# Attenuator.net
KiCad netlist of a schematic drawn in EAGLE
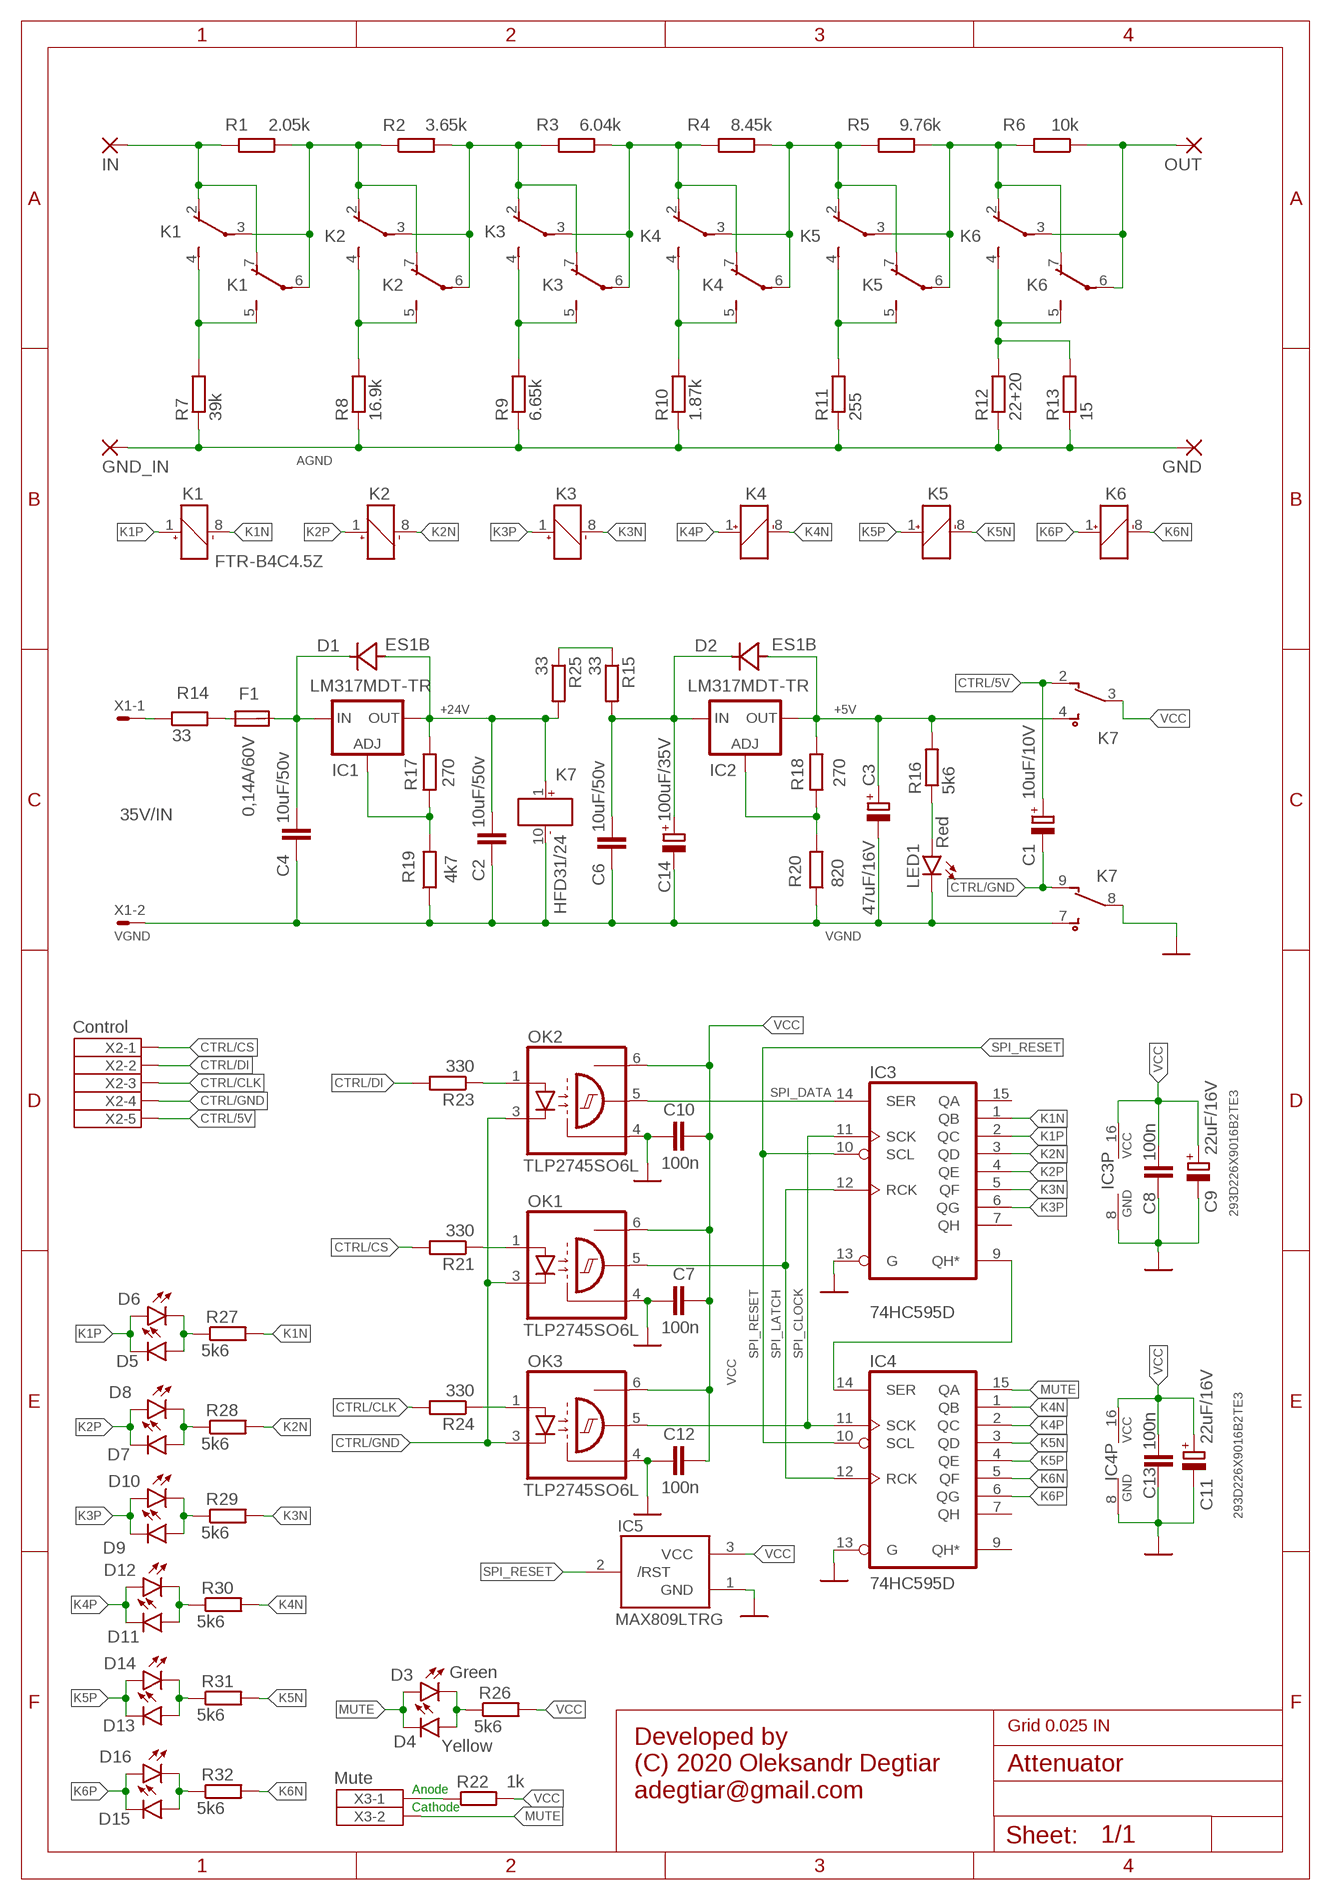
[diagram p0: schematic, sheet 1]

(export (version "E")
  (design (tool "Eeschema 10.0.6"))
  (components
    (comp (ref "C1")
      (value "10uF/10V")
      (footprint "eagle-import:SMC_A")
      (fields (field (name "PARTNAME") "TAJA106K010RNJ"))
      (libsource (lib "eagle-import") (part "rcl_334_CPOL-EUSMCA"))
    )
    (comp (ref "C2")
      (value "10uF/50v")
      (footprint "eagle-import:C1206")
      (libsource (lib "eagle-import") (part "C-EUC1206"))
    )
    (comp (ref "C3")
      (value "47uF/16V")
      (footprint "eagle-import:SMC_C")
      (libsource (lib "eagle-import") (part "rcl_334_CPOL-EUSMCC"))
    )
    (comp (ref "C4")
      (value "10uF/50v")
      (footprint "eagle-import:C1206")
      (libsource (lib "eagle-import") (part "C-EUC1206"))
    )
    (comp (ref "C6")
      (value "10uF/50v")
      (footprint "eagle-import:C1206")
      (libsource (lib "eagle-import") (part "C-EUC1206"))
    )
    (comp (ref "C7")
      (value "100n")
      (footprint "eagle-import:C0603")
      (libsource (lib "eagle-import") (part "C-EUC0603"))
    )
    (comp (ref "C8")
      (value "100n")
      (footprint "eagle-import:C0603")
      (libsource (lib "eagle-import") (part "C-EUC0603"))
    )
    (comp (ref "C9")
      (value "22uF/16V")
      (footprint "eagle-import:SMC_B")
      (fields (field (name "PARTNAME") "293D226X9016B2TE3"))
      (libsource (lib "eagle-import") (part "rcl_334_CPOL-EUSMCB"))
    )
    (comp (ref "C10")
      (value "100n")
      (footprint "eagle-import:C0603")
      (libsource (lib "eagle-import") (part "C-EUC0603"))
    )
    (comp (ref "C11")
      (value "22uF/16V")
      (footprint "eagle-import:SMC_B")
      (fields (field (name "PARTNAME") "293D226X9016B2TE3"))
      (libsource (lib "eagle-import") (part "rcl_334_CPOL-EUSMCB"))
    )
    (comp (ref "C12")
      (value "100n")
      (footprint "eagle-import:C0603")
      (libsource (lib "eagle-import") (part "C-EUC0603"))
    )
    (comp (ref "C13")
      (value "100n")
      (footprint "eagle-import:C0603")
      (libsource (lib "eagle-import") (part "C-EUC0603"))
    )
    (comp (ref "C14")
      (value "100uF/35V")
      (footprint "eagle-import:UD-6,3X5,8_NICHICON")
      (fields (field (name "PARTNAME") "EEEFK1V101XP"))
      (libsource (lib "eagle-import") (part "CPOL-EUUD-6,3X8,8"))
    )
    (comp (ref "D1")
      (value "ES1B")
      (footprint "eagle-import:SMA")
      (libsource (lib "eagle-import") (part "MBRA340T3"))
    )
    (comp (ref "D2")
      (value "ES1B")
      (footprint "eagle-import:SMA")
      (libsource (lib "eagle-import") (part "MBRA340T3"))
    )
    (comp (ref "D3")
      (value "Green")
      (footprint "eagle-import:CHIPLED_0805")
      (libsource (lib "eagle-import") (part "LEDCHIPLED_0805"))
    )
    (comp (ref "D4")
      (value "Yellow")
      (footprint "eagle-import:CHIPLED_0805")
      (libsource (lib "eagle-import") (part "LEDCHIPLED_0805"))
    )
    (comp (ref "D5")
      (value "LEDCHIPLED_0805")
      (footprint "eagle-import:CHIPLED_0805")
      (libsource (lib "eagle-import") (part "LEDCHIPLED_0805"))
    )
    (comp (ref "D6")
      (value "LEDCHIPLED_0805")
      (footprint "eagle-import:CHIPLED_0805")
      (libsource (lib "eagle-import") (part "LEDCHIPLED_0805"))
    )
    (comp (ref "D7")
      (value "LEDCHIPLED_0805")
      (footprint "eagle-import:CHIPLED_0805")
      (libsource (lib "eagle-import") (part "LEDCHIPLED_0805"))
    )
    (comp (ref "D8")
      (value "LEDCHIPLED_0805")
      (footprint "eagle-import:CHIPLED_0805")
      (libsource (lib "eagle-import") (part "LEDCHIPLED_0805"))
    )
    (comp (ref "D9")
      (value "LEDCHIPLED_0805")
      (footprint "eagle-import:CHIPLED_0805")
      (libsource (lib "eagle-import") (part "LEDCHIPLED_0805"))
    )
    (comp (ref "D10")
      (value "LEDCHIPLED_0805")
      (footprint "eagle-import:CHIPLED_0805")
      (libsource (lib "eagle-import") (part "LEDCHIPLED_0805"))
    )
    (comp (ref "D11")
      (value "LEDCHIPLED_0805")
      (footprint "eagle-import:CHIPLED_0805")
      (libsource (lib "eagle-import") (part "LEDCHIPLED_0805"))
    )
    (comp (ref "D12")
      (value "LEDCHIPLED_0805")
      (footprint "eagle-import:CHIPLED_0805")
      (libsource (lib "eagle-import") (part "LEDCHIPLED_0805"))
    )
    (comp (ref "D13")
      (value "LEDCHIPLED_0805")
      (footprint "eagle-import:CHIPLED_0805")
      (libsource (lib "eagle-import") (part "LEDCHIPLED_0805"))
    )
    (comp (ref "D14")
      (value "LEDCHIPLED_0805")
      (footprint "eagle-import:CHIPLED_0805")
      (libsource (lib "eagle-import") (part "LEDCHIPLED_0805"))
    )
    (comp (ref "D15")
      (value "LEDCHIPLED_0805")
      (footprint "eagle-import:CHIPLED_0805")
      (libsource (lib "eagle-import") (part "LEDCHIPLED_0805"))
    )
    (comp (ref "D16")
      (value "LEDCHIPLED_0805")
      (footprint "eagle-import:CHIPLED_0805")
      (libsource (lib "eagle-import") (part "LEDCHIPLED_0805"))
    )
    (comp (ref "F1")
      (value "0,14A/60V")
      (footprint "eagle-import:MF-MSMF010-2")
      (libsource (lib "eagle-import") (part "MF-MSMF010-2"))
    )
    (comp (ref "GND")
      (value "OUT_GND")
      (footprint "eagle-import:2,54_1,1")
      (libsource (lib "eagle-import") (part "2,54/1,1"))
    )
    (comp (ref "GND_IN")
      (value "IN_GND")
      (footprint "eagle-import:2,54_1,1")
      (libsource (lib "eagle-import") (part "2,54/1,1"))
    )
    (comp (ref "IC1")
      (value "LM317MDT-TR")
      (footprint "eagle-import:DPACK")
      (libsource (lib "eagle-import") (part "LM317?MBDTRK"))
    )
    (comp (ref "IC2")
      (value "LM317MDT-TR")
      (footprint "eagle-import:DPACK")
      (libsource (lib "eagle-import") (part "LM317?MDT"))
    )
    (comp (ref "IC3")
      (value "74HC595D")
      (footprint "eagle-import:SO16")
      (libsource (lib "eagle-import") (part "74595DHC"))
    )
    (comp (ref "IC4")
      (value "74HC595D")
      (footprint "eagle-import:SO16")
      (libsource (lib "eagle-import") (part "74595DHC"))
    )
    (comp (ref "IC5")
      (value "MAX809LTRG")
      (footprint "eagle-import:SOT23")
      (libsource (lib "eagle-import") (part "MAX809EURJ"))
    )
    (comp (ref "IN")
      (value "IN")
      (footprint "eagle-import:2,54_1,1")
      (libsource (lib "eagle-import") (part "2,54/1,1"))
    )
    (comp (ref "K1")
      (value "FTR-B4C4.5Z")
      (footprint "eagle-import:FTR-B4C")
      (libsource (lib "eagle-import") (part "FTR-B4C"))
    )
    (comp (ref "K2")
      (value "FTR-B4C4.5Z")
      (footprint "eagle-import:FTR-B4C")
      (libsource (lib "eagle-import") (part "FTR-B4C"))
    )
    (comp (ref "K3")
      (value "FTR-B4C4.5Z")
      (footprint "eagle-import:FTR-B4C")
      (libsource (lib "eagle-import") (part "FTR-B4C"))
    )
    (comp (ref "K4")
      (value "FTR-B4C4.5Z")
      (footprint "eagle-import:FTR-B4C")
      (libsource (lib "eagle-import") (part "FTR-B4C"))
    )
    (comp (ref "K5")
      (value "FTR-B4C4.5Z")
      (footprint "eagle-import:FTR-B4C")
      (libsource (lib "eagle-import") (part "FTR-B4C"))
    )
    (comp (ref "K6")
      (value "FTR-B4C4.5Z")
      (footprint "eagle-import:FTR-B4C")
      (libsource (lib "eagle-import") (part "FTR-B4C"))
    )
    (comp (ref "K7")
      (value "HFD31/24")
      (footprint "eagle-import:HFD31")
      (libsource (lib "eagle-import") (part "HFD31"))
    )
    (comp (ref "LED1")
      (value "Red")
      (footprint "eagle-import:CHIPLED_0805")
      (libsource (lib "eagle-import") (part "LEDCHIPLED_0805"))
    )
    (comp (ref "OK1")
      (value "TLP2745SO6L")
      (footprint "eagle-import:SO6L")
      (libsource (lib "eagle-import") (part "TLP2745SO6L"))
    )
    (comp (ref "OK2")
      (value "TLP2745SO6L")
      (footprint "eagle-import:SO6L")
      (libsource (lib "eagle-import") (part "TLP2745SO6L"))
    )
    (comp (ref "OK3")
      (value "TLP2745SO6L")
      (footprint "eagle-import:SO6L")
      (libsource (lib "eagle-import") (part "TLP2745SO6L"))
    )
    (comp (ref "OUT")
      (value "OUT")
      (footprint "eagle-import:2,54_1,1")
      (libsource (lib "eagle-import") (part "2,54/1,1"))
    )
    (comp (ref "R1")
      (value "2.05k")
      (footprint "eagle-import:R0805")
      (libsource (lib "eagle-import") (part "R-EU_R0805"))
    )
    (comp (ref "R2")
      (value "3.65k")
      (footprint "eagle-import:R0805")
      (libsource (lib "eagle-import") (part "R-EU_R0805"))
    )
    (comp (ref "R3")
      (value "6.04k")
      (footprint "eagle-import:R0805")
      (libsource (lib "eagle-import") (part "R-EU_R0805"))
    )
    (comp (ref "R4")
      (value "8.45k")
      (footprint "eagle-import:R0805")
      (libsource (lib "eagle-import") (part "R-EU_R0805"))
    )
    (comp (ref "R5")
      (value "9.76k")
      (footprint "eagle-import:R0805")
      (libsource (lib "eagle-import") (part "R-EU_R0805"))
    )
    (comp (ref "R6")
      (value "10k")
      (footprint "eagle-import:R0805")
      (libsource (lib "eagle-import") (part "R-EU_R0805"))
    )
    (comp (ref "R7")
      (value "39k")
      (footprint "eagle-import:R0805")
      (libsource (lib "eagle-import") (part "R-EU_R0805"))
    )
    (comp (ref "R8")
      (value "16.9k")
      (footprint "eagle-import:R0805")
      (libsource (lib "eagle-import") (part "R-EU_R0805"))
    )
    (comp (ref "R9")
      (value "6.65k")
      (footprint "eagle-import:R0805")
      (libsource (lib "eagle-import") (part "R-EU_R0805"))
    )
    (comp (ref "R10")
      (value "1.87k")
      (footprint "eagle-import:R0805")
      (libsource (lib "eagle-import") (part "R-EU_R0805"))
    )
    (comp (ref "R11")
      (value "255")
      (footprint "eagle-import:R0805")
      (libsource (lib "eagle-import") (part "R-EU_R0805"))
    )
    (comp (ref "R12")
      (value "22+20")
      (footprint "eagle-import:R0805")
      (libsource (lib "eagle-import") (part "R-EU_R0805"))
    )
    (comp (ref "R13")
      (value "15")
      (footprint "eagle-import:R0805")
      (libsource (lib "eagle-import") (part "R-EU_R0805"))
    )
    (comp (ref "R14")
      (value "33")
      (footprint "eagle-import:R1206")
      (libsource (lib "eagle-import") (part "R-EU_R1206"))
    )
    (comp (ref "R15")
      (value "33")
      (footprint "eagle-import:R1206")
      (libsource (lib "eagle-import") (part "R-EU_R1206"))
    )
    (comp (ref "R16")
      (value "5k6")
      (footprint "eagle-import:R0805")
      (libsource (lib "eagle-import") (part "R-EU_R0805"))
    )
    (comp (ref "R17")
      (value "270")
      (footprint "eagle-import:R0805")
      (libsource (lib "eagle-import") (part "R-EU_R0805"))
    )
    (comp (ref "R18")
      (value "270")
      (footprint "eagle-import:R0805")
      (libsource (lib "eagle-import") (part "R-EU_R0805"))
    )
    (comp (ref "R19")
      (value "4k7")
      (footprint "eagle-import:R0805")
      (libsource (lib "eagle-import") (part "R-EU_R0805"))
    )
    (comp (ref "R20")
      (value "820")
      (footprint "eagle-import:R0805")
      (libsource (lib "eagle-import") (part "R-EU_R0805"))
    )
    (comp (ref "R21")
      (value "330")
      (footprint "eagle-import:R0805")
      (libsource (lib "eagle-import") (part "rcl_334_R-EU_R0805"))
    )
    (comp (ref "R22")
      (value "1k")
      (footprint "eagle-import:R0805")
      (libsource (lib "eagle-import") (part "R-EU_R0805"))
    )
    (comp (ref "R23")
      (value "330")
      (footprint "eagle-import:R0805")
      (libsource (lib "eagle-import") (part "rcl_334_R-EU_R0805"))
    )
    (comp (ref "R24")
      (value "330")
      (footprint "eagle-import:R0805")
      (libsource (lib "eagle-import") (part "rcl_334_R-EU_R0805"))
    )
    (comp (ref "R25")
      (value "33")
      (footprint "eagle-import:R1206")
      (libsource (lib "eagle-import") (part "R-EU_R1206"))
    )
    (comp (ref "R26")
      (value "5k6")
      (footprint "eagle-import:R0805")
      (libsource (lib "eagle-import") (part "R-EU_R0805"))
    )
    (comp (ref "R27")
      (value "5k6")
      (footprint "eagle-import:R0805")
      (libsource (lib "eagle-import") (part "R-EU_R0805"))
    )
    (comp (ref "R28")
      (value "5k6")
      (footprint "eagle-import:R0805")
      (libsource (lib "eagle-import") (part "R-EU_R0805"))
    )
    (comp (ref "R29")
      (value "5k6")
      (footprint "eagle-import:R0805")
      (libsource (lib "eagle-import") (part "R-EU_R0805"))
    )
    (comp (ref "R30")
      (value "5k6")
      (footprint "eagle-import:R0805")
      (libsource (lib "eagle-import") (part "R-EU_R0805"))
    )
    (comp (ref "R31")
      (value "5k6")
      (footprint "eagle-import:R0805")
      (libsource (lib "eagle-import") (part "R-EU_R0805"))
    )
    (comp (ref "R32")
      (value "5k6")
      (footprint "eagle-import:R0805")
      (libsource (lib "eagle-import") (part "R-EU_R0805"))
    )
    (comp (ref "X1")
      (value "35V/IN")
      (footprint "eagle-import:KK-156-2")
      (fields (field (name "MF") "MOLEX"))
      (libsource (lib "eagle-import") (part "KK-156-2"))
    )
    (comp (ref "X2")
      (value "Control")
      (footprint "eagle-import:JST-XH-05-PACKAGE-ROUND-PAD")
      (libsource (lib "eagle-import") (part "JST-XH-05-PIN-ROUND-PAD"))
    )
    (comp (ref "X3")
      (value "Mute")
      (footprint "eagle-import:JST-XH-02-PACKAGE-ROUND-PAD")
      (libsource (lib "eagle-import") (part "JST-XH-02-PIN-ROUND-PAD"))
    )
  )
  (nets
    (net (code "1") (name "/+5V") (class "Default")
      (node (ref "C3") (pin "+") (pinfunction "+_+") (pintype "passive"))
      (node (ref "D2") (pin "A") (pinfunction "A_A") (pintype "passive"))
      (node (ref "IC2") (pin "4") (pinfunction "OUT_4") (pintype "passive"))
      (node (ref "K7") (pin "4") (pinfunction "NO_4") (pintype "passive"))
      (node (ref "R16") (pin "2") (pinfunction "2_2") (pintype "passive"))
      (node (ref "R18") (pin "1") (pinfunction "1_1") (pintype "passive"))
    )
    (net (code "2") (name "/+24V") (class "Default")
      (node (ref "C2") (pin "1") (pinfunction "1_1") (pintype "passive"))
      (node (ref "D1") (pin "A") (pinfunction "A_A") (pintype "passive"))
      (node (ref "IC1") (pin "4") (pinfunction "OUT_4") (pintype "passive"))
      (node (ref "K7") (pin "1") (pinfunction "+_1") (pintype "bidirectional"))
      (node (ref "R17") (pin "1") (pinfunction "1_1") (pintype "passive"))
      (node (ref "R25") (pin "2") (pinfunction "2_2") (pintype "passive"))
    )
    (net (code "3") (name "/AGND") (class "Default")
      (node (ref "GND") (pin "1") (pinfunction "P_1") (pintype "passive"))
      (node (ref "GND_IN") (pin "1") (pinfunction "P_1") (pintype "passive"))
      (node (ref "R10") (pin "1") (pinfunction "1_1") (pintype "passive"))
      (node (ref "R11") (pin "1") (pinfunction "1_1") (pintype "passive"))
      (node (ref "R12") (pin "1") (pinfunction "1_1") (pintype "passive"))
      (node (ref "R13") (pin "1") (pinfunction "1_1") (pintype "passive"))
      (node (ref "R7") (pin "1") (pinfunction "1_1") (pintype "passive"))
      (node (ref "R8") (pin "1") (pinfunction "1_1") (pintype "passive"))
      (node (ref "R9") (pin "1") (pinfunction "1_1") (pintype "passive"))
    )
    (net (code "4") (name "/SPI_CLOCK") (class "Default")
      (node (ref "IC3") (pin "11") (pinfunction "SCK_11") (pintype "input"))
      (node (ref "IC4") (pin "11") (pinfunction "SCK_11") (pintype "input"))
      (node (ref "OK3") (pin "5") (pinfunction "OUT_5") (pintype "passive"))
    )
    (net (code "5") (name "/SPI_DATA") (class "Default")
      (node (ref "IC3") (pin "14") (pinfunction "SER_14") (pintype "input"))
      (node (ref "OK2") (pin "5") (pinfunction "OUT_5") (pintype "passive"))
    )
    (net (code "6") (name "/SPI_LATCH") (class "Default")
      (node (ref "IC3") (pin "12") (pinfunction "RCK_12") (pintype "input"))
      (node (ref "IC4") (pin "12") (pinfunction "RCK_12") (pintype "input"))
      (node (ref "OK1") (pin "5") (pinfunction "OUT_5") (pintype "passive"))
    )
    (net (code "7") (name "/VGND") (class "Default")
      (node (ref "C14") (pin "-") (pinfunction "-_-") (pintype "passive"))
      (node (ref "C2") (pin "2") (pinfunction "2_2") (pintype "passive"))
      (node (ref "C3") (pin "-") (pinfunction "-_-") (pintype "passive"))
      (node (ref "C4") (pin "2") (pinfunction "2_2") (pintype "passive"))
      (node (ref "C6") (pin "2") (pinfunction "2_2") (pintype "passive"))
      (node (ref "K7") (pin "10") (pinfunction "-_10") (pintype "bidirectional"))
      (node (ref "K7") (pin "7") (pinfunction "NO_7") (pintype "passive"))
      (node (ref "LED1") (pin "C") (pinfunction "C_C") (pintype "passive"))
      (node (ref "R19") (pin "1") (pinfunction "1_1") (pintype "passive"))
      (node (ref "R20") (pin "1") (pinfunction "1_1") (pintype "passive"))
      (node (ref "X1") (pin "2") (pinfunction "S_2") (pintype "passive"))
    )
    (net (code "8") (name "CTRL{slash}5V") (class "Default")
      (node (ref "C1") (pin "+") (pinfunction "+_+") (pintype "passive"))
      (node (ref "K7") (pin "2") (pinfunction "NC_2") (pintype "passive"))
      (node (ref "X2") (pin "5") (pinfunction "S_5") (pintype "passive"))
    )
    (net (code "9") (name "CTRL{slash}CLK") (class "Default")
      (node (ref "R24") (pin "2") (pinfunction "2_2") (pintype "passive"))
      (node (ref "X2") (pin "3") (pinfunction "S_3") (pintype "passive"))
    )
    (net (code "10") (name "CTRL{slash}CS") (class "Default")
      (node (ref "R21") (pin "2") (pinfunction "2_2") (pintype "passive"))
      (node (ref "X2") (pin "1") (pinfunction "S_1") (pintype "passive"))
    )
    (net (code "11") (name "CTRL{slash}DI") (class "Default")
      (node (ref "R23") (pin "2") (pinfunction "2_2") (pintype "passive"))
      (node (ref "X2") (pin "2") (pinfunction "S_2") (pintype "passive"))
    )
    (net (code "12") (name "CTRL{slash}GND") (class "Default")
      (node (ref "C1") (pin "-") (pinfunction "-_-") (pintype "passive"))
      (node (ref "K7") (pin "9") (pinfunction "NC_9") (pintype "passive"))
      (node (ref "OK1") (pin "3") (pinfunction "C_3") (pintype "passive"))
      (node (ref "OK2") (pin "3") (pinfunction "C_3") (pintype "passive"))
      (node (ref "OK3") (pin "3") (pinfunction "C_3") (pintype "passive"))
      (node (ref "X2") (pin "4") (pinfunction "S_4") (pintype "passive"))
    )
    (net (code "13") (name "GND") (class "Default")
      (node (ref "C10") (pin "2") (pinfunction "2_2") (pintype "passive"))
      (node (ref "C11") (pin "-") (pinfunction "-_-") (pintype "passive"))
      (node (ref "C12") (pin "2") (pinfunction "2_2") (pintype "passive"))
      (node (ref "C13") (pin "1") (pinfunction "1_1") (pintype "passive"))
      (node (ref "C7") (pin "2") (pinfunction "2_2") (pintype "passive"))
      (node (ref "C8") (pin "2") (pinfunction "2_2") (pintype "passive"))
      (node (ref "C9") (pin "-") (pinfunction "-_-") (pintype "passive"))
      (node (ref "IC3") (pin "13") (pinfunction "G_13") (pintype "input"))
      (node (ref "IC3") (pin "8") (pinfunction "GND_8") (pintype "power_in"))
      (node (ref "IC4") (pin "13") (pinfunction "G_13") (pintype "input"))
      (node (ref "IC4") (pin "8") (pinfunction "GND_8") (pintype "power_in"))
      (node (ref "IC5") (pin "1") (pinfunction "GND_1") (pintype "power_in"))
      (node (ref "K7") (pin "8") (pinfunction "COM_8") (pintype "passive"))
      (node (ref "OK1") (pin "4") (pinfunction "GND_4") (pintype "passive"))
      (node (ref "OK2") (pin "4") (pinfunction "GND_4") (pintype "passive"))
      (node (ref "OK3") (pin "4") (pinfunction "GND_4") (pintype "passive"))
    )
    (net (code "14") (name "K1N") (class "Default")
      (node (ref "IC3") (pin "1") (pinfunction "QB_1") (pintype "tri_state"))
      (node (ref "K1") (pin "8") (pinfunction "-_8") (pintype "passive"))
      (node (ref "R27") (pin "2") (pinfunction "2_2") (pintype "passive"))
    )
    (net (code "15") (name "K1P") (class "Default")
      (node (ref "D5") (pin "C") (pinfunction "C_C") (pintype "passive"))
      (node (ref "D6") (pin "A") (pinfunction "A_A") (pintype "passive"))
      (node (ref "IC3") (pin "2") (pinfunction "QC_2") (pintype "tri_state"))
      (node (ref "K1") (pin "1") (pinfunction "+_1") (pintype "passive"))
    )
    (net (code "16") (name "K2N") (class "Default")
      (node (ref "IC3") (pin "3") (pinfunction "QD_3") (pintype "tri_state"))
      (node (ref "K2") (pin "8") (pinfunction "-_8") (pintype "passive"))
      (node (ref "R28") (pin "2") (pinfunction "2_2") (pintype "passive"))
    )
    (net (code "17") (name "K2P") (class "Default")
      (node (ref "D7") (pin "C") (pinfunction "C_C") (pintype "passive"))
      (node (ref "D8") (pin "A") (pinfunction "A_A") (pintype "passive"))
      (node (ref "IC3") (pin "4") (pinfunction "QE_4") (pintype "tri_state"))
      (node (ref "K2") (pin "1") (pinfunction "+_1") (pintype "passive"))
    )
    (net (code "18") (name "K3N") (class "Default")
      (node (ref "IC3") (pin "5") (pinfunction "QF_5") (pintype "tri_state"))
      (node (ref "K3") (pin "8") (pinfunction "-_8") (pintype "passive"))
      (node (ref "R29") (pin "2") (pinfunction "2_2") (pintype "passive"))
    )
    (net (code "19") (name "K3P") (class "Default")
      (node (ref "D10") (pin "A") (pinfunction "A_A") (pintype "passive"))
      (node (ref "D9") (pin "C") (pinfunction "C_C") (pintype "passive"))
      (node (ref "IC3") (pin "6") (pinfunction "QG_6") (pintype "tri_state"))
      (node (ref "K3") (pin "1") (pinfunction "+_1") (pintype "passive"))
    )
    (net (code "20") (name "K4N") (class "Default")
      (node (ref "IC4") (pin "1") (pinfunction "QB_1") (pintype "tri_state"))
      (node (ref "K4") (pin "8") (pinfunction "-_8") (pintype "passive"))
      (node (ref "R30") (pin "2") (pinfunction "2_2") (pintype "passive"))
    )
    (net (code "21") (name "K4P") (class "Default")
      (node (ref "D11") (pin "C") (pinfunction "C_C") (pintype "passive"))
      (node (ref "D12") (pin "A") (pinfunction "A_A") (pintype "passive"))
      (node (ref "IC4") (pin "2") (pinfunction "QC_2") (pintype "tri_state"))
      (node (ref "K4") (pin "1") (pinfunction "+_1") (pintype "passive"))
    )
    (net (code "22") (name "K5N") (class "Default")
      (node (ref "IC4") (pin "3") (pinfunction "QD_3") (pintype "tri_state"))
      (node (ref "K5") (pin "8") (pinfunction "-_8") (pintype "passive"))
      (node (ref "R31") (pin "2") (pinfunction "2_2") (pintype "passive"))
    )
    (net (code "23") (name "K5P") (class "Default")
      (node (ref "D13") (pin "C") (pinfunction "C_C") (pintype "passive"))
      (node (ref "D14") (pin "A") (pinfunction "A_A") (pintype "passive"))
      (node (ref "IC4") (pin "4") (pinfunction "QE_4") (pintype "tri_state"))
      (node (ref "K5") (pin "1") (pinfunction "+_1") (pintype "passive"))
    )
    (net (code "24") (name "K6N") (class "Default")
      (node (ref "IC4") (pin "5") (pinfunction "QF_5") (pintype "tri_state"))
      (node (ref "K6") (pin "8") (pinfunction "-_8") (pintype "passive"))
      (node (ref "R32") (pin "2") (pinfunction "2_2") (pintype "passive"))
    )
    (net (code "25") (name "K6P") (class "Default")
      (node (ref "D15") (pin "C") (pinfunction "C_C") (pintype "passive"))
      (node (ref "D16") (pin "A") (pinfunction "A_A") (pintype "passive"))
      (node (ref "IC4") (pin "6") (pinfunction "QG_6") (pintype "tri_state"))
      (node (ref "K6") (pin "1") (pinfunction "+_1") (pintype "passive"))
    )
    (net (code "26") (name "MUTE") (class "Default")
      (node (ref "D3") (pin "A") (pinfunction "A_A") (pintype "passive"))
      (node (ref "D4") (pin "C") (pinfunction "C_C") (pintype "passive"))
      (node (ref "IC4") (pin "15") (pinfunction "QA_15") (pintype "tri_state"))
      (node (ref "X3") (pin "2") (pinfunction "S_2") (pintype "passive"))
    )
    (net (code "27") (name "Net-(D3-PadC)") (class "Default")
      (node (ref "D3") (pin "C") (pinfunction "C_C") (pintype "passive"))
      (node (ref "D4") (pin "A") (pinfunction "A_A") (pintype "passive"))
      (node (ref "R26") (pin "1") (pinfunction "1_1") (pintype "passive"))
    )
    (net (code "28") (name "Net-(D5-PadA)") (class "Default")
      (node (ref "D5") (pin "A") (pinfunction "A_A") (pintype "passive"))
      (node (ref "D6") (pin "C") (pinfunction "C_C") (pintype "passive"))
      (node (ref "R27") (pin "1") (pinfunction "1_1") (pintype "passive"))
    )
    (net (code "29") (name "Net-(D7-PadA)") (class "Default")
      (node (ref "D7") (pin "A") (pinfunction "A_A") (pintype "passive"))
      (node (ref "D8") (pin "C") (pinfunction "C_C") (pintype "passive"))
      (node (ref "R28") (pin "1") (pinfunction "1_1") (pintype "passive"))
    )
    (net (code "30") (name "Net-(D10-PadC)") (class "Default")
      (node (ref "D10") (pin "C") (pinfunction "C_C") (pintype "passive"))
      (node (ref "D9") (pin "A") (pinfunction "A_A") (pintype "passive"))
      (node (ref "R29") (pin "1") (pinfunction "1_1") (pintype "passive"))
    )
    (net (code "31") (name "Net-(D11-PadA)") (class "Default")
      (node (ref "D11") (pin "A") (pinfunction "A_A") (pintype "passive"))
      (node (ref "D12") (pin "C") (pinfunction "C_C") (pintype "passive"))
      (node (ref "R30") (pin "1") (pinfunction "1_1") (pintype "passive"))
    )
    (net (code "32") (name "Net-(D13-PadA)") (class "Default")
      (node (ref "D13") (pin "A") (pinfunction "A_A") (pintype "passive"))
      (node (ref "D14") (pin "C") (pinfunction "C_C") (pintype "passive"))
      (node (ref "R31") (pin "1") (pinfunction "1_1") (pintype "passive"))
    )
    (net (code "33") (name "Net-(D15-PadA)") (class "Default")
      (node (ref "D15") (pin "A") (pinfunction "A_A") (pintype "passive"))
      (node (ref "D16") (pin "C") (pinfunction "C_C") (pintype "passive"))
      (node (ref "R32") (pin "1") (pinfunction "1_1") (pintype "passive"))
    )
    (net (code "34") (name "Net-(F1-Pad1)") (class "Default")
      (node (ref "F1") (pin "1") (pinfunction "1_1") (pintype "passive"))
      (node (ref "R14") (pin "2") (pinfunction "2_2") (pintype "passive"))
    )
    (net (code "35") (name "Net-(IC1-ADJ)") (class "Default")
      (node (ref "IC1") (pin "1") (pinfunction "ADJ_1") (pintype "input"))
      (node (ref "R17") (pin "2") (pinfunction "2_2") (pintype "passive"))
      (node (ref "R19") (pin "2") (pinfunction "2_2") (pintype "passive"))
    )
    (net (code "36") (name "Net-(IC1-IN)") (class "Default")
      (node (ref "C4") (pin "1") (pinfunction "1_1") (pintype "passive"))
      (node (ref "D1") (pin "C") (pinfunction "C_C") (pintype "passive"))
      (node (ref "F1") (pin "2") (pinfunction "2_2") (pintype "passive"))
      (node (ref "IC1") (pin "3") (pinfunction "IN_3") (pintype "input"))
    )
    (net (code "37") (name "Net-(IC2-ADJ)") (class "Default")
      (node (ref "IC2") (pin "1") (pinfunction "ADJ_1") (pintype "input"))
      (node (ref "R18") (pin "2") (pinfunction "2_2") (pintype "passive"))
      (node (ref "R20") (pin "2") (pinfunction "2_2") (pintype "passive"))
    )
    (net (code "38") (name "Net-(IC2-IN)") (class "Default")
      (node (ref "C14") (pin "+") (pinfunction "+_+") (pintype "passive"))
      (node (ref "C6") (pin "1") (pinfunction "1_1") (pintype "passive"))
      (node (ref "D2") (pin "C") (pinfunction "C_C") (pintype "passive"))
      (node (ref "IC2") (pin "3") (pinfunction "IN_3") (pintype "input"))
      (node (ref "R15") (pin "2") (pinfunction "2_2") (pintype "passive"))
    )
    (net (code "39") (name "Net-(IC3A-QH*)") (class "Default")
      (node (ref "IC3") (pin "9") (pinfunction "QH*_9") (pintype "tri_state"))
      (node (ref "IC4") (pin "14") (pinfunction "SER_14") (pintype "input"))
    )
    (net (code "40") (name "Net-(IN-P)") (class "Default")
      (node (ref "IN") (pin "1") (pinfunction "P_1") (pintype "passive"))
      (node (ref "K1") (pin "2") (pinfunction "O_2") (pintype "passive"))
      (node (ref "K1") (pin "7") (pinfunction "O_7") (pintype "passive"))
      (node (ref "R1") (pin "2") (pinfunction "2_2") (pintype "passive"))
    )
    (net (code "41") (name "Net-(K1A-P)") (class "Default")
      (node (ref "K1") (pin "3") (pinfunction "P_3") (pintype "passive"))
      (node (ref "K1") (pin "6") (pinfunction "P_6") (pintype "passive"))
      (node (ref "K2") (pin "2") (pinfunction "O_2") (pintype "passive"))
      (node (ref "K2") (pin "7") (pinfunction "O_7") (pintype "passive"))
      (node (ref "R1") (pin "1") (pinfunction "1_1") (pintype "passive"))
      (node (ref "R2") (pin "1") (pinfunction "1_1") (pintype "passive"))
    )
    (net (code "42") (name "Net-(K1A-S)") (class "Default")
      (node (ref "K1") (pin "4") (pinfunction "S_4") (pintype "passive"))
      (node (ref "K1") (pin "5") (pinfunction "S_5") (pintype "passive"))
      (node (ref "R7") (pin "2") (pinfunction "2_2") (pintype "passive"))
    )
    (net (code "43") (name "Net-(K2A-P)") (class "Default")
      (node (ref "K2") (pin "3") (pinfunction "P_3") (pintype "passive"))
      (node (ref "K2") (pin "6") (pinfunction "P_6") (pintype "passive"))
      (node (ref "K3") (pin "2") (pinfunction "O_2") (pintype "passive"))
      (node (ref "K3") (pin "7") (pinfunction "O_7") (pintype "passive"))
      (node (ref "R2") (pin "2") (pinfunction "2_2") (pintype "passive"))
      (node (ref "R3") (pin "2") (pinfunction "2_2") (pintype "passive"))
    )
    (net (code "44") (name "Net-(K2A-S)") (class "Default")
      (node (ref "K2") (pin "4") (pinfunction "S_4") (pintype "passive"))
      (node (ref "K2") (pin "5") (pinfunction "S_5") (pintype "passive"))
      (node (ref "R8") (pin "2") (pinfunction "2_2") (pintype "passive"))
    )
    (net (code "45") (name "Net-(K3A-P)") (class "Default")
      (node (ref "K3") (pin "3") (pinfunction "P_3") (pintype "passive"))
      (node (ref "K3") (pin "6") (pinfunction "P_6") (pintype "passive"))
      (node (ref "K4") (pin "2") (pinfunction "O_2") (pintype "passive"))
      (node (ref "K4") (pin "7") (pinfunction "O_7") (pintype "passive"))
      (node (ref "R3") (pin "1") (pinfunction "1_1") (pintype "passive"))
      (node (ref "R4") (pin "2") (pinfunction "2_2") (pintype "passive"))
    )
    (net (code "46") (name "Net-(K3A-S)") (class "Default")
      (node (ref "K3") (pin "4") (pinfunction "S_4") (pintype "passive"))
      (node (ref "K3") (pin "5") (pinfunction "S_5") (pintype "passive"))
      (node (ref "R9") (pin "2") (pinfunction "2_2") (pintype "passive"))
    )
    (net (code "47") (name "Net-(K4A-P)") (class "Default")
      (node (ref "K4") (pin "3") (pinfunction "P_3") (pintype "passive"))
      (node (ref "K4") (pin "6") (pinfunction "P_6") (pintype "passive"))
      (node (ref "K5") (pin "2") (pinfunction "O_2") (pintype "passive"))
      (node (ref "K5") (pin "7") (pinfunction "O_7") (pintype "passive"))
      (node (ref "R4") (pin "1") (pinfunction "1_1") (pintype "passive"))
      (node (ref "R5") (pin "2") (pinfunction "2_2") (pintype "passive"))
    )
    (net (code "48") (name "Net-(K4A-S)") (class "Default")
      (node (ref "K4") (pin "4") (pinfunction "S_4") (pintype "passive"))
      (node (ref "K4") (pin "5") (pinfunction "S_5") (pintype "passive"))
      (node (ref "R10") (pin "2") (pinfunction "2_2") (pintype "passive"))
    )
    (net (code "49") (name "Net-(K5A-P)") (class "Default")
      (node (ref "K5") (pin "3") (pinfunction "P_3") (pintype "passive"))
      (node (ref "K5") (pin "6") (pinfunction "P_6") (pintype "passive"))
      (node (ref "K6") (pin "2") (pinfunction "O_2") (pintype "passive"))
      (node (ref "K6") (pin "7") (pinfunction "O_7") (pintype "passive"))
      (node (ref "R5") (pin "1") (pinfunction "1_1") (pintype "passive"))
      (node (ref "R6") (pin "2") (pinfunction "2_2") (pintype "passive"))
    )
    (net (code "50") (name "Net-(K5A-S)") (class "Default")
      (node (ref "K5") (pin "4") (pinfunction "S_4") (pintype "passive"))
      (node (ref "K5") (pin "5") (pinfunction "S_5") (pintype "passive"))
      (node (ref "R11") (pin "2") (pinfunction "2_2") (pintype "passive"))
    )
    (net (code "51") (name "Net-(K6A-P)") (class "Default")
      (node (ref "K6") (pin "3") (pinfunction "P_3") (pintype "passive"))
      (node (ref "K6") (pin "6") (pinfunction "P_6") (pintype "passive"))
      (node (ref "OUT") (pin "1") (pinfunction "P_1") (pintype "passive"))
      (node (ref "R6") (pin "1") (pinfunction "1_1") (pintype "passive"))
    )
    (net (code "52") (name "Net-(K6A-S)") (class "Default")
      (node (ref "K6") (pin "4") (pinfunction "S_4") (pintype "passive"))
      (node (ref "K6") (pin "5") (pinfunction "S_5") (pintype "passive"))
      (node (ref "R12") (pin "2") (pinfunction "2_2") (pintype "passive"))
      (node (ref "R13") (pin "2") (pinfunction "2_2") (pintype "passive"))
    )
    (net (code "53") (name "Net-(LED1-PadA)") (class "Default")
      (node (ref "LED1") (pin "A") (pinfunction "A_A") (pintype "passive"))
      (node (ref "R16") (pin "1") (pinfunction "1_1") (pintype "passive"))
    )
    (net (code "54") (name "Net-(OK1-A)") (class "Default")
      (node (ref "OK1") (pin "1") (pinfunction "A_1") (pintype "passive"))
      (node (ref "R21") (pin "1") (pinfunction "1_1") (pintype "passive"))
    )
    (net (code "55") (name "Net-(OK2-A)") (class "Default")
      (node (ref "OK2") (pin "1") (pinfunction "A_1") (pintype "passive"))
      (node (ref "R23") (pin "1") (pinfunction "1_1") (pintype "passive"))
    )
    (net (code "56") (name "Net-(OK3-A)") (class "Default")
      (node (ref "OK3") (pin "1") (pinfunction "A_1") (pintype "passive"))
      (node (ref "R24") (pin "1") (pinfunction "1_1") (pintype "passive"))
    )
    (net (code "57") (name "Net-(R15-Pad1)") (class "Default")
      (node (ref "R15") (pin "1") (pinfunction "1_1") (pintype "passive"))
      (node (ref "R25") (pin "1") (pinfunction "1_1") (pintype "passive"))
    )
    (net (code "58") (name "Net-(X1A-S)") (class "Default")
      (node (ref "R14") (pin "1") (pinfunction "1_1") (pintype "passive"))
      (node (ref "X1") (pin "1") (pinfunction "S_1") (pintype "passive"))
    )
    (net (code "59") (name "Net-(X3A-S)") (class "Default")
      (node (ref "R22") (pin "1") (pinfunction "1_1") (pintype "passive"))
      (node (ref "X3") (pin "1") (pinfunction "S_1") (pintype "passive"))
    )
    (net (code "60") (name "SPI_RESET") (class "Default")
      (node (ref "IC3") (pin "10") (pinfunction "SCL_10") (pintype "input"))
      (node (ref "IC4") (pin "10") (pinfunction "SCL_10") (pintype "input"))
      (node (ref "IC5") (pin "2") (pinfunction "/RST_2") (pintype "output"))
    )
    (net (code "61") (name "VCC") (class "Default")
      (node (ref "C10") (pin "1") (pinfunction "1_1") (pintype "passive"))
      (node (ref "C11") (pin "+") (pinfunction "+_+") (pintype "passive"))
      (node (ref "C12") (pin "1") (pinfunction "1_1") (pintype "passive"))
      (node (ref "C13") (pin "2") (pinfunction "2_2") (pintype "passive"))
      (node (ref "C7") (pin "1") (pinfunction "1_1") (pintype "passive"))
      (node (ref "C8") (pin "1") (pinfunction "1_1") (pintype "passive"))
      (node (ref "C9") (pin "+") (pinfunction "+_+") (pintype "passive"))
      (node (ref "IC3") (pin "16") (pinfunction "VCC_16") (pintype "power_in"))
      (node (ref "IC4") (pin "16") (pinfunction "VCC_16") (pintype "power_in"))
      (node (ref "IC5") (pin "3") (pinfunction "VCC_3") (pintype "input"))
      (node (ref "K7") (pin "3") (pinfunction "COM_3") (pintype "passive"))
      (node (ref "OK1") (pin "6") (pinfunction "VCC_6") (pintype "passive"))
      (node (ref "OK2") (pin "6") (pinfunction "VCC_6") (pintype "passive"))
      (node (ref "OK3") (pin "6") (pinfunction "VCC_6") (pintype "passive"))
      (node (ref "R22") (pin "2") (pinfunction "2_2") (pintype "passive"))
      (node (ref "R26") (pin "2") (pinfunction "2_2") (pintype "passive"))
    )
    (net (code "62") (name "unconnected-(IC3A-QA-Pad15)") (class "Default")
      (node (ref "IC3") (pin "15") (pinfunction "QA_15") (pintype "tri_state"))
    )
    (net (code "63") (name "unconnected-(IC3A-QH-Pad7)") (class "Default")
      (node (ref "IC3") (pin "7") (pinfunction "QH_7") (pintype "tri_state"))
    )
    (net (code "64") (name "unconnected-(IC4A-QH*-Pad9)") (class "Default")
      (node (ref "IC4") (pin "9") (pinfunction "QH*_9") (pintype "tri_state"))
    )
    (net (code "65") (name "unconnected-(IC4A-QH-Pad7)") (class "Default")
      (node (ref "IC4") (pin "7") (pinfunction "QH_7") (pintype "tri_state"))
    )
  )
)
